# Lower.net
KiCad netlist of a schematic drawn in Altium Designer
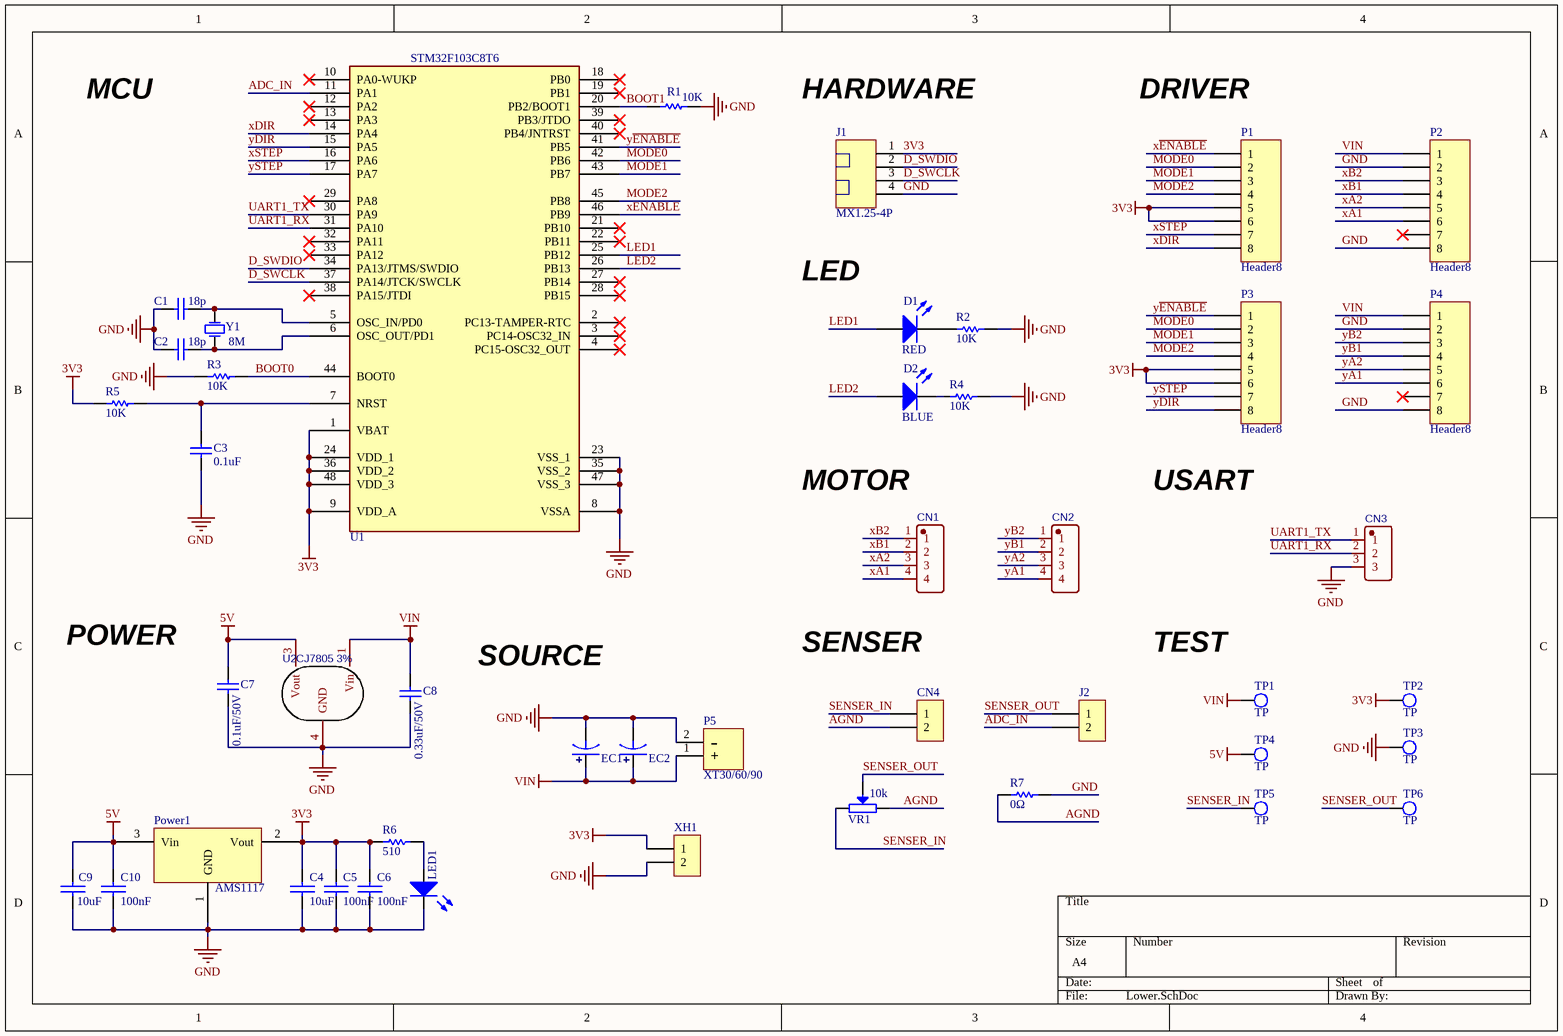
[diagram p0: Lower.SchDoc]

(export (version "E")
  (design (tool "Eeschema 10.0.6"))
  (components
    (comp (ref "C1")
      (value "18p")
      (footprint "0603C")
      (description "Capacitor")
      (fields (field (name "Comment") "Cap") (field (name "PUBLISHER") "Altium Limited"))
      (libsource (lib "Miscellaneous Devices") (part "Cap"))
    )
    (comp (ref "C2")
      (value "18p")
      (footprint "0603C")
      (description "Capacitor")
      (fields (field (name "Comment") "Cap") (field (name "PUBLISHER") "Altium Limited"))
      (libsource (lib "Miscellaneous Devices") (part "Cap"))
    )
    (comp (ref "C3")
      (value "0.1uF")
      (footprint "0603C")
      (description "Capacitor")
      (fields (field (name "Comment") "C0603") (field (name "PUBLISHER") "Altium Limited"))
      (libsource (lib "MYLIB") (part "C-RAD-0603"))
    )
    (comp (ref "C4")
      (value "10uF")
      (footprint "0805c")
      (description "无极性电容")
      (libsource (lib "电容") (part "CAP"))
    )
    (comp (ref "C5")
      (value "100nF")
      (footprint "0603C")
      (description "无极性电容")
      (libsource (lib "电容") (part "CAP"))
    )
    (comp (ref "C6")
      (value "100nF")
      (footprint "0603C")
      (description "无极性电容")
      (libsource (lib "电容") (part "CAP"))
    )
    (comp (ref "C7")
      (value "0.1uF/50V")
      (footprint "0603C")
      (description "Capacitor")
      (fields (field (name "PUBLISHER") "Altium Limited"))
      (libsource (lib "MyComponents_v2.5") (part "Cap"))
    )
    (comp (ref "C8")
      (value "0.33uF/50V")
      (footprint "0603C")
      (description "Capacitor")
      (fields (field (name "PUBLISHER") "Altium Limited"))
      (libsource (lib "MyComponents_v2.5") (part "Cap"))
    )
    (comp (ref "C9")
      (value "10uF")
      (footprint "0805c")
      (description "无极性电容")
      (libsource (lib "电容") (part "CAP"))
    )
    (comp (ref "C10")
      (value "100nF")
      (footprint "0603C")
      (description "无极性电容")
      (libsource (lib "电容") (part "CAP"))
    )
    (comp (ref "CN1")
      (value "HX25003-4A")
      (footprint "XH4/2.54mm/90")
      (fields (field (name "BOM_SUPPLIER PART") "C442301") (field (name "CONTRIBUTOR") "LCSC"))
      (libsource (lib "altium-import") (part "root_0_HX25003-4A_"))
    )
    (comp (ref "CN2")
      (value "HX25003-4A")
      (footprint "XH4/2.54mm/90")
      (fields (field (name "BOM_SUPPLIER PART") "C442301") (field (name "CONTRIBUTOR") "LCSC"))
      (libsource (lib "altium-import") (part "root_0_HX25003-4A_"))
    )
    (comp (ref "CN3")
      (value "X8821WR-03S-N0SN")
      (footprint "XH3/2.54mm/90")
      (fields (field (name "BOM_SUPPLIER PART") "C388740") (field (name "CONTRIBUTOR") "LCSC"))
      (libsource (lib "altium-import") (part "root_0_X8821WR-03S-N0SN_"))
    )
    (comp (ref "CN4") (value "XH2") (footprint "XH2/2.54mm/90") (libsource (lib "XH，VH") (part "XH2")))
    (comp (ref "D1")
      (value "RED")
      (footprint "0603LED_B")
      (description "Typical RED, GREEN, YELLOW, AMBER GaAs LED")
      (fields (field (name "PUBLISHER") "Altium Limited"))
      (libsource (lib "MYLIB") (part "D0603"))
    )
    (comp (ref "D2")
      (value "BLUE")
      (footprint "0603LED_B")
      (description "Typical RED, GREEN, YELLOW, AMBER GaAs LED")
      (fields (field (name "PUBLISHER") "Altium Limited"))
      (libsource (lib "MYLIB") (part "D0603"))
    )
    (comp (ref "EC1")
      (value "DIP_ECAP")
      (footprint "DIP-EC2.0X5X11-A")
      (description "直插电解电容")
      (libsource (lib "电容") (part "DIP_ECAP"))
    )
    (comp (ref "EC2")
      (value "DIP_ECAP")
      (footprint "DIP-EC2.0X5X11-A")
      (description "直插电解电容")
      (libsource (lib "电容") (part "DIP_ECAP"))
    )
    (comp (ref "J1") (value "MX1.25-4P") (footprint "MX1.25WS-4P") (libsource (lib "MX") (part "MX1.25-4P")))
    (comp (ref "J2")
      (value "Pin HDR1X2")
      (footprint "Pin HDR1X2/2.54mm-S")
      (libsource (lib "排针") (part "Pin HDR1X2"))
    )
    (comp (ref "LED1")
      (value "LED_RED")
      (footprint "0603LED_R")
      (description "Typical RED, GREEN, YELLOW, AMBER GaAs LED")
      (fields (field (name "PUBLISHER") "Altium Limited"))
      (libsource (lib "MyComponents_v2.5") (part "LED"))
    )
    (comp (ref "P1")
      (value "Header8")
      (footprint "HEADER 8x1")
      (libsource (lib "MyComponents_v2.5") (part "Header 8"))
    )
    (comp (ref "P2")
      (value "Header8")
      (footprint "HEADER 8x1")
      (libsource (lib "MyComponents_v2.5") (part "Header 8"))
    )
    (comp (ref "P3")
      (value "Header8")
      (footprint "HEADER 8x1")
      (libsource (lib "MyComponents_v2.5") (part "Header 8"))
    )
    (comp (ref "P4")
      (value "Header8")
      (footprint "HEADER 8x1")
      (libsource (lib "MyComponents_v2.5") (part "Header 8"))
    )
    (comp (ref "P5")
      (value "XT30/60/90")
      (footprint "XT30PW-Male")
      (libsource (lib "MyComponents_v2.5") (part "XT30/60/90"))
    )
    (comp (ref "Power1")
      (value "AMS1117")
      (footprint "SOT223")
      (description "三端稳压芯片")
      (libsource (lib "电源芯片") (part "AMS1117"))
    )
    (comp (ref "R1")
      (value "10K")
      (footprint "0603R")
      (description "Resistor")
      (fields (field (name "Comment") "R0603") (field (name "PUBLISHER") "Altium Limited"))
      (libsource (lib "电阻") (part "R0603"))
    )
    (comp (ref "R2")
      (value "10K")
      (footprint "0603R")
      (description "Resistor")
      (fields (field (name "Comment") "R0603") (field (name "PUBLISHER") "Altium Limited"))
      (libsource (lib "电阻") (part "0603-1"))
    )
    (comp (ref "R3")
      (value "10K")
      (footprint "0603R")
      (description "Resistor")
      (fields (field (name "Comment") "R0603") (field (name "PUBLISHER") "Altium Limited"))
      (libsource (lib "电阻") (part "0603-1"))
    )
    (comp (ref "R4")
      (value "10K")
      (footprint "0603R")
      (description "Resistor")
      (fields (field (name "Comment") "R0603") (field (name "PUBLISHER") "Altium Limited"))
      (libsource (lib "电阻") (part "0603-1"))
    )
    (comp (ref "R5")
      (value "10K")
      (footprint "0603R")
      (description "Resistor")
      (fields (field (name "Comment") "R0603") (field (name "PUBLISHER") "Altium Limited"))
      (libsource (lib "电阻") (part "0603-1"))
    )
    (comp (ref "R6") (value "510") (footprint "0603R") (libsource (lib "电阻") (part "RES")))
    (comp (ref "R7") (value "0Ω") (footprint "0603R") (libsource (lib "电阻") (part "RES")))
    (comp (ref "TP1")
      (value "TP")
      (footprint "TP_SMT")
      (description "Test Point")
      (libsource (lib "MyComponents_v2.5") (part "TP"))
    )
    (comp (ref "TP2")
      (value "TP")
      (footprint "TP_SMT")
      (description "Test Point")
      (libsource (lib "MyComponents_v2.5") (part "TP"))
    )
    (comp (ref "TP3")
      (value "TP")
      (footprint "TP_SMT")
      (description "Test Point")
      (libsource (lib "MyComponents_v2.5") (part "TP"))
    )
    (comp (ref "TP4")
      (value "TP")
      (footprint "TP_SMT")
      (description "Test Point")
      (libsource (lib "MyComponents_v2.5") (part "TP"))
    )
    (comp (ref "TP5")
      (value "TP")
      (footprint "TP_SMT")
      (description "Test Point")
      (libsource (lib "MyComponents_v2.5") (part "TP"))
    )
    (comp (ref "TP6")
      (value "TP")
      (footprint "TP_SMT")
      (description "Test Point")
      (libsource (lib "MyComponents_v2.5") (part "TP"))
    )
    (comp (ref "U1")
      (value "STM32F103C8T6")
      (footprint "LQFP_48")
      (description "LowPower MCU")
      (libsource (lib "MYLIB") (part "STM32F103C8T6"))
    )
    (comp (ref "U2")
      (value "CJ7805 3%")
      (footprint "7805-foot")
      (fields (field (name "BOM_SUPPLIER PART") "C21706"))
      (libsource (lib "altium-import") (part "root_1_CJ7805 3%_"))
    )
    (comp (ref "VR1") (value "10k") (footprint "3296W") (libsource (lib "电阻") (part "RESVR")))
    (comp (ref "XH1") (value "XH2") (footprint "XH2/2.54mm/90") (libsource (lib "XH，VH") (part "XH2")))
    (comp (ref "Y1")
      (value "8M")
      (footprint "NX5032GA")
      (description "Crystal Oscillator")
      (fields (field (name "PUBLISHER") "Altium Limited"))
      (libsource (lib "MyComponents") (part "XTAL"))
    )
  )
  (nets
    (net (code "1") (name "/ADC_IN") (class "Default")
      (node (ref "J2") (pin "2") (pinfunction "2_2") (pintype "passive"))
      (node (ref "U1") (pin "11") (pinfunction "PA1_11") (pintype "passive"))
    )
    (net (code "2") (name "/AGND") (class "Default")
      (node (ref "CN4") (pin "2") (pinfunction "2_2") (pintype "passive"))
      (node (ref "R7") (pin "1") (pinfunction "1_1") (pintype "passive"))
      (node (ref "VR1") (pin "2") (pinfunction "2_2") (pintype "passive"))
    )
    (net (code "3") (name "/BOOT0") (class "Default")
      (node (ref "R3") (pin "1") (pinfunction "1_1") (pintype "passive"))
      (node (ref "U1") (pin "44") (pinfunction "BOOT0_44") (pintype "passive"))
    )
    (net (code "4") (name "/BOOT1") (class "Default")
      (node (ref "R1") (pin "2") (pinfunction "2_2") (pintype "passive"))
      (node (ref "U1") (pin "20") (pinfunction "PB2/BOOT1_20") (pintype "passive"))
    )
    (net (code "5") (name "/D_SWCLK") (class "Default")
      (node (ref "J1") (pin "3") (pinfunction "3_3") (pintype "passive"))
      (node (ref "U1") (pin "37") (pinfunction "PA14/JTCK/SWCLK_37") (pintype "passive"))
    )
    (net (code "6") (name "/D_SWDIO") (class "Default")
      (node (ref "J1") (pin "2") (pinfunction "2_2") (pintype "passive"))
      (node (ref "U1") (pin "34") (pinfunction "PA13/JTMS/SWDIO_34") (pintype "passive"))
    )
    (net (code "7") (name "/LED1") (class "Default")
      (node (ref "D1") (pin "1") (pinfunction "A_1") (pintype "passive"))
      (node (ref "U1") (pin "25") (pinfunction "PB12_25") (pintype "passive"))
    )
    (net (code "8") (name "/LED2") (class "Default")
      (node (ref "D2") (pin "1") (pinfunction "A_1") (pintype "passive"))
      (node (ref "U1") (pin "26") (pinfunction "PB13_26") (pintype "passive"))
    )
    (net (code "9") (name "/MODE0") (class "Default")
      (node (ref "P1") (pin "2") (pinfunction "2_2") (pintype "passive"))
      (node (ref "P3") (pin "2") (pinfunction "2_2") (pintype "passive"))
      (node (ref "U1") (pin "42") (pinfunction "PB6_42") (pintype "passive"))
    )
    (net (code "10") (name "/MODE1") (class "Default")
      (node (ref "P1") (pin "3") (pinfunction "3_3") (pintype "passive"))
      (node (ref "P3") (pin "3") (pinfunction "3_3") (pintype "passive"))
      (node (ref "U1") (pin "43") (pinfunction "PB7_43") (pintype "passive"))
    )
    (net (code "11") (name "/MODE2") (class "Default")
      (node (ref "P1") (pin "4") (pinfunction "4_4") (pintype "passive"))
      (node (ref "P3") (pin "4") (pinfunction "4_4") (pintype "passive"))
      (node (ref "U1") (pin "45") (pinfunction "PB8_45") (pintype "passive"))
    )
    (net (code "12") (name "/SENSER_IN") (class "Default")
      (node (ref "CN4") (pin "1") (pinfunction "1_1") (pintype "passive"))
      (node (ref "TP5") (pin "1") (pinfunction "TP_1") (pintype "open_collector"))
      (node (ref "VR1") (pin "1") (pinfunction "1_1") (pintype "passive"))
    )
    (net (code "13") (name "/SENSER_OUT") (class "Default")
      (node (ref "J2") (pin "1") (pinfunction "1_1") (pintype "passive"))
      (node (ref "TP6") (pin "1") (pinfunction "TP_1") (pintype "open_collector"))
      (node (ref "VR1") (pin "2") (pinfunction "2_2") (pintype "passive"))
    )
    (net (code "14") (name "/UART1_RX") (class "Default")
      (node (ref "CN3") (pin "2") (pinfunction "2_2") (pintype "passive"))
      (node (ref "U1") (pin "31") (pinfunction "PA10_31") (pintype "passive"))
    )
    (net (code "15") (name "/UART1_TX") (class "Default")
      (node (ref "CN3") (pin "1") (pinfunction "1_1") (pintype "passive"))
      (node (ref "U1") (pin "30") (pinfunction "PA9_30") (pintype "passive"))
    )
    (net (code "16") (name "/xA1") (class "Default")
      (node (ref "CN1") (pin "4") (pinfunction "4_4") (pintype "passive"))
      (node (ref "P2") (pin "6") (pinfunction "6_6") (pintype "passive"))
    )
    (net (code "17") (name "/xA2") (class "Default")
      (node (ref "CN1") (pin "3") (pinfunction "3_3") (pintype "passive"))
      (node (ref "P2") (pin "5") (pinfunction "5_5") (pintype "passive"))
    )
    (net (code "18") (name "/xB1") (class "Default")
      (node (ref "CN1") (pin "2") (pinfunction "2_2") (pintype "passive"))
      (node (ref "P2") (pin "4") (pinfunction "4_4") (pintype "passive"))
    )
    (net (code "19") (name "/xB2") (class "Default")
      (node (ref "CN1") (pin "1") (pinfunction "1_1") (pintype "passive"))
      (node (ref "P2") (pin "3") (pinfunction "3_3") (pintype "passive"))
    )
    (net (code "20") (name "/xDIR") (class "Default")
      (node (ref "P1") (pin "8") (pinfunction "8_8") (pintype "passive"))
      (node (ref "U1") (pin "14") (pinfunction "PA4_14") (pintype "passive"))
    )
    (net (code "21") (name "/xSTEP") (class "Default")
      (node (ref "P1") (pin "7") (pinfunction "7_7") (pintype "passive"))
      (node (ref "U1") (pin "16") (pinfunction "PA6_16") (pintype "passive"))
    )
    (net (code "22") (name "/x~{ENABLE}") (class "Default")
      (node (ref "P1") (pin "1") (pinfunction "1_1") (pintype "passive"))
      (node (ref "U1") (pin "46") (pinfunction "PB9_46") (pintype "passive"))
    )
    (net (code "23") (name "/yA1") (class "Default")
      (node (ref "CN2") (pin "4") (pinfunction "4_4") (pintype "passive"))
      (node (ref "P4") (pin "6") (pinfunction "6_6") (pintype "passive"))
    )
    (net (code "24") (name "/yA2") (class "Default")
      (node (ref "CN2") (pin "3") (pinfunction "3_3") (pintype "passive"))
      (node (ref "P4") (pin "5") (pinfunction "5_5") (pintype "passive"))
    )
    (net (code "25") (name "/yB1") (class "Default")
      (node (ref "CN2") (pin "2") (pinfunction "2_2") (pintype "passive"))
      (node (ref "P4") (pin "4") (pinfunction "4_4") (pintype "passive"))
    )
    (net (code "26") (name "/yB2") (class "Default")
      (node (ref "CN2") (pin "1") (pinfunction "1_1") (pintype "passive"))
      (node (ref "P4") (pin "3") (pinfunction "3_3") (pintype "passive"))
    )
    (net (code "27") (name "/yDIR") (class "Default")
      (node (ref "P3") (pin "8") (pinfunction "8_8") (pintype "passive"))
      (node (ref "U1") (pin "15") (pinfunction "PA5_15") (pintype "passive"))
    )
    (net (code "28") (name "/ySTEP") (class "Default")
      (node (ref "P3") (pin "7") (pinfunction "7_7") (pintype "passive"))
      (node (ref "U1") (pin "17") (pinfunction "PA7_17") (pintype "passive"))
    )
    (net (code "29") (name "/y~{ENABLE}") (class "Default")
      (node (ref "P3") (pin "1") (pinfunction "1_1") (pintype "passive"))
      (node (ref "U1") (pin "41") (pinfunction "PB5_41") (pintype "passive"))
    )
    (net (code "30") (name "3V3") (class "Default")
      (node (ref "C4") (pin "2") (pinfunction "2_2") (pintype "passive"))
      (node (ref "C5") (pin "2") (pinfunction "2_2") (pintype "passive"))
      (node (ref "C6") (pin "2") (pinfunction "2_2") (pintype "passive"))
      (node (ref "J1") (pin "1") (pinfunction "1_1") (pintype "passive"))
      (node (ref "P1") (pin "5") (pinfunction "5_5") (pintype "passive"))
      (node (ref "P1") (pin "6") (pinfunction "6_6") (pintype "passive"))
      (node (ref "P3") (pin "5") (pinfunction "5_5") (pintype "passive"))
      (node (ref "P3") (pin "6") (pinfunction "6_6") (pintype "passive"))
      (node (ref "Power1") (pin "2") (pinfunction "Vout_2") (pintype "passive"))
      (node (ref "R5") (pin "2") (pinfunction "2_2") (pintype "passive"))
      (node (ref "R6") (pin "1") (pinfunction "1_1") (pintype "passive"))
      (node (ref "TP2") (pin "1") (pinfunction "TP_1") (pintype "open_collector"))
      (node (ref "U1") (pin "1") (pinfunction "VBAT_1") (pintype "passive"))
      (node (ref "U1") (pin "24") (pinfunction "VDD_1_24") (pintype "passive"))
      (node (ref "U1") (pin "36") (pinfunction "VDD_2_36") (pintype "passive"))
      (node (ref "U1") (pin "48") (pinfunction "VDD_3_48") (pintype "passive"))
      (node (ref "U1") (pin "9") (pinfunction "VDD_A_9") (pintype "passive"))
      (node (ref "XH1") (pin "1") (pinfunction "1_1") (pintype "passive"))
    )
    (net (code "31") (name "5V") (class "Default")
      (node (ref "C10") (pin "2") (pinfunction "2_2") (pintype "passive"))
      (node (ref "C7") (pin "1") (pinfunction "1_1") (pintype "passive"))
      (node (ref "C9") (pin "2") (pinfunction "2_2") (pintype "passive"))
      (node (ref "Power1") (pin "3") (pinfunction "Vin_3") (pintype "passive"))
      (node (ref "TP4") (pin "1") (pinfunction "TP_1") (pintype "open_collector"))
      (node (ref "U2") (pin "3") (pinfunction "Vout_3") (pintype "passive"))
    )
    (net (code "32") (name "GND") (class "Default")
      (node (ref "C1") (pin "2") (pinfunction "2_2") (pintype "passive"))
      (node (ref "C10") (pin "1") (pinfunction "1_1") (pintype "passive"))
      (node (ref "C2") (pin "2") (pinfunction "2_2") (pintype "passive"))
      (node (ref "C3") (pin "1") (pinfunction "1_1") (pintype "passive"))
      (node (ref "C4") (pin "1") (pinfunction "1_1") (pintype "passive"))
      (node (ref "C5") (pin "1") (pinfunction "1_1") (pintype "passive"))
      (node (ref "C6") (pin "1") (pinfunction "1_1") (pintype "passive"))
      (node (ref "C7") (pin "2") (pinfunction "2_2") (pintype "passive"))
      (node (ref "C8") (pin "2") (pinfunction "2_2") (pintype "passive"))
      (node (ref "C9") (pin "1") (pinfunction "1_1") (pintype "passive"))
      (node (ref "CN3") (pin "3") (pinfunction "3_3") (pintype "passive"))
      (node (ref "EC1") (pin "2") (pinfunction "2_2") (pintype "passive"))
      (node (ref "EC2") (pin "2") (pinfunction "2_2") (pintype "passive"))
      (node (ref "J1") (pin "4") (pinfunction "4_4") (pintype "passive"))
      (node (ref "LED1") (pin "2") (pinfunction "2_2") (pintype "passive"))
      (node (ref "P2") (pin "2") (pinfunction "2_2") (pintype "passive"))
      (node (ref "P2") (pin "8") (pinfunction "8_8") (pintype "passive"))
      (node (ref "P4") (pin "2") (pinfunction "2_2") (pintype "passive"))
      (node (ref "P4") (pin "8") (pinfunction "8_8") (pintype "passive"))
      (node (ref "P5") (pin "2") (pinfunction "-_2") (pintype "passive"))
      (node (ref "Power1") (pin "1") (pinfunction "GND_1") (pintype "passive"))
      (node (ref "R1") (pin "1") (pinfunction "1_1") (pintype "passive"))
      (node (ref "R2") (pin "1") (pinfunction "1_1") (pintype "passive"))
      (node (ref "R3") (pin "2") (pinfunction "2_2") (pintype "passive"))
      (node (ref "R4") (pin "1") (pinfunction "1_1") (pintype "passive"))
      (node (ref "R7") (pin "2") (pinfunction "2_2") (pintype "passive"))
      (node (ref "TP3") (pin "1") (pinfunction "TP_1") (pintype "open_collector"))
      (node (ref "U1") (pin "23") (pinfunction "VSS_1_23") (pintype "passive"))
      (node (ref "U1") (pin "35") (pinfunction "VSS_2_35") (pintype "passive"))
      (node (ref "U1") (pin "47") (pinfunction "VSS_3_47") (pintype "passive"))
      (node (ref "U1") (pin "8") (pinfunction "VSSA_8") (pintype "passive"))
      (node (ref "U2") (pin "4") (pinfunction "GND_4") (pintype "passive"))
      (node (ref "XH1") (pin "2") (pinfunction "2_2") (pintype "passive"))
    )
    (net (code "33") (name "Net-(D1-K)") (class "Default")
      (node (ref "D1") (pin "2") (pinfunction "K_2") (pintype "passive"))
      (node (ref "R2") (pin "2") (pinfunction "2_2") (pintype "passive"))
    )
    (net (code "34") (name "Net-(D2-K)") (class "Default")
      (node (ref "D2") (pin "2") (pinfunction "K_2") (pintype "passive"))
      (node (ref "R4") (pin "2") (pinfunction "2_2") (pintype "passive"))
    )
    (net (code "35") (name "Net-(LED1-Pad1)") (class "Default")
      (node (ref "LED1") (pin "1") (pinfunction "1_1") (pintype "passive"))
      (node (ref "R6") (pin "2") (pinfunction "2_2") (pintype "passive"))
    )
    (net (code "36") (name "Net-(U1-NRST)") (class "Default")
      (node (ref "C3") (pin "2") (pinfunction "2_2") (pintype "passive"))
      (node (ref "R5") (pin "1") (pinfunction "1_1") (pintype "passive"))
      (node (ref "U1") (pin "7") (pinfunction "NRST_7") (pintype "passive"))
    )
    (net (code "37") (name "Net-(U1-OSC_IN{slash}PD0)") (class "Default")
      (node (ref "C1") (pin "1") (pinfunction "1_1") (pintype "passive"))
      (node (ref "U1") (pin "5") (pinfunction "OSC_IN/PD0_5") (pintype "passive"))
      (node (ref "Y1") (pin "2") (pinfunction "OSC2_2") (pintype "passive"))
    )
    (net (code "38") (name "Net-(U1-OSC_OUT{slash}PD1)") (class "Default")
      (node (ref "C2") (pin "1") (pinfunction "1_1") (pintype "passive"))
      (node (ref "U1") (pin "6") (pinfunction "OSC_OUT/PD1_6") (pintype "passive"))
      (node (ref "Y1") (pin "1") (pinfunction "OSC1_1") (pintype "passive"))
    )
    (net (code "39") (name "VIN") (class "Default")
      (node (ref "C8") (pin "1") (pinfunction "1_1") (pintype "passive"))
      (node (ref "EC1") (pin "1") (pinfunction "1_1") (pintype "passive"))
      (node (ref "EC2") (pin "1") (pinfunction "1_1") (pintype "passive"))
      (node (ref "P2") (pin "1") (pinfunction "1_1") (pintype "passive"))
      (node (ref "P4") (pin "1") (pinfunction "1_1") (pintype "passive"))
      (node (ref "P5") (pin "1") (pinfunction "+_1") (pintype "passive"))
      (node (ref "TP1") (pin "1") (pinfunction "TP_1") (pintype "open_collector"))
      (node (ref "U2") (pin "1") (pinfunction "Vin_1") (pintype "passive"))
    )
    (net (code "40") (name "unconnected-(P2-Pad7)") (class "Default")
      (node (ref "P2") (pin "7") (pinfunction "7_7") (pintype "passive+no_connect"))
    )
    (net (code "41") (name "unconnected-(P4-Pad7)") (class "Default")
      (node (ref "P4") (pin "7") (pinfunction "7_7") (pintype "passive+no_connect"))
    )
    (net (code "42") (name "unconnected-(U1-PA0-WUKP-Pad10)") (class "Default")
      (node (ref "U1") (pin "10") (pinfunction "PA0-WUKP_10") (pintype "passive+no_connect"))
    )
    (net (code "43") (name "unconnected-(U1-PA2-Pad12)") (class "Default")
      (node (ref "U1") (pin "12") (pinfunction "PA2_12") (pintype "passive+no_connect"))
    )
    (net (code "44") (name "unconnected-(U1-PA3-Pad13)") (class "Default")
      (node (ref "U1") (pin "13") (pinfunction "PA3_13") (pintype "passive+no_connect"))
    )
    (net (code "45") (name "unconnected-(U1-PA8-Pad29)") (class "Default")
      (node (ref "U1") (pin "29") (pinfunction "PA8_29") (pintype "passive+no_connect"))
    )
    (net (code "46") (name "unconnected-(U1-PA11-Pad32)") (class "Default")
      (node (ref "U1") (pin "32") (pinfunction "PA11_32") (pintype "passive+no_connect"))
    )
    (net (code "47") (name "unconnected-(U1-PA12-Pad33)") (class "Default")
      (node (ref "U1") (pin "33") (pinfunction "PA12_33") (pintype "passive+no_connect"))
    )
    (net (code "48") (name "unconnected-(U1-PA15{slash}JTDI-Pad38)") (class "Default")
      (node (ref "U1") (pin "38") (pinfunction "PA15/JTDI_38") (pintype "passive+no_connect"))
    )
    (net (code "49") (name "unconnected-(U1-PB0-Pad18)") (class "Default")
      (node (ref "U1") (pin "18") (pinfunction "PB0_18") (pintype "passive+no_connect"))
    )
    (net (code "50") (name "unconnected-(U1-PB1-Pad19)") (class "Default")
      (node (ref "U1") (pin "19") (pinfunction "PB1_19") (pintype "passive+no_connect"))
    )
    (net (code "51") (name "unconnected-(U1-PB3{slash}JTDO-Pad39)") (class "Default")
      (node (ref "U1") (pin "39") (pinfunction "PB3/JTDO_39") (pintype "passive+no_connect"))
    )
    (net (code "52") (name "unconnected-(U1-PB4{slash}JNTRST-Pad40)") (class "Default")
      (node (ref "U1") (pin "40") (pinfunction "PB4/JNTRST_40") (pintype "passive+no_connect"))
    )
    (net (code "53") (name "unconnected-(U1-PB10-Pad21)") (class "Default")
      (node (ref "U1") (pin "21") (pinfunction "PB10_21") (pintype "passive+no_connect"))
    )
    (net (code "54") (name "unconnected-(U1-PB11-Pad22)") (class "Default")
      (node (ref "U1") (pin "22") (pinfunction "PB11_22") (pintype "passive+no_connect"))
    )
    (net (code "55") (name "unconnected-(U1-PB14-Pad27)") (class "Default")
      (node (ref "U1") (pin "27") (pinfunction "PB14_27") (pintype "passive+no_connect"))
    )
    (net (code "56") (name "unconnected-(U1-PB15-Pad28)") (class "Default")
      (node (ref "U1") (pin "28") (pinfunction "PB15_28") (pintype "passive+no_connect"))
    )
    (net (code "57") (name "unconnected-(U1-PC13-TAMPER-RTC-Pad2)") (class "Default")
      (node (ref "U1") (pin "2") (pinfunction "PC13-TAMPER-RTC_2") (pintype "passive+no_connect"))
    )
    (net (code "58") (name "unconnected-(U1-PC14-OSC32_IN-Pad3)") (class "Default")
      (node (ref "U1") (pin "3") (pinfunction "PC14-OSC32_IN_3") (pintype "passive+no_connect"))
    )
    (net (code "59") (name "unconnected-(U1-PC15-OSC32_OUT-Pad4)") (class "Default")
      (node (ref "U1") (pin "4") (pinfunction "PC15-OSC32_OUT_4") (pintype "passive+no_connect"))
    )
  )
)
